# SCH_27C160-Replacement-Adapter_2025-10-2.net
KiCad netlist of a schematic drawn in EasyEDA
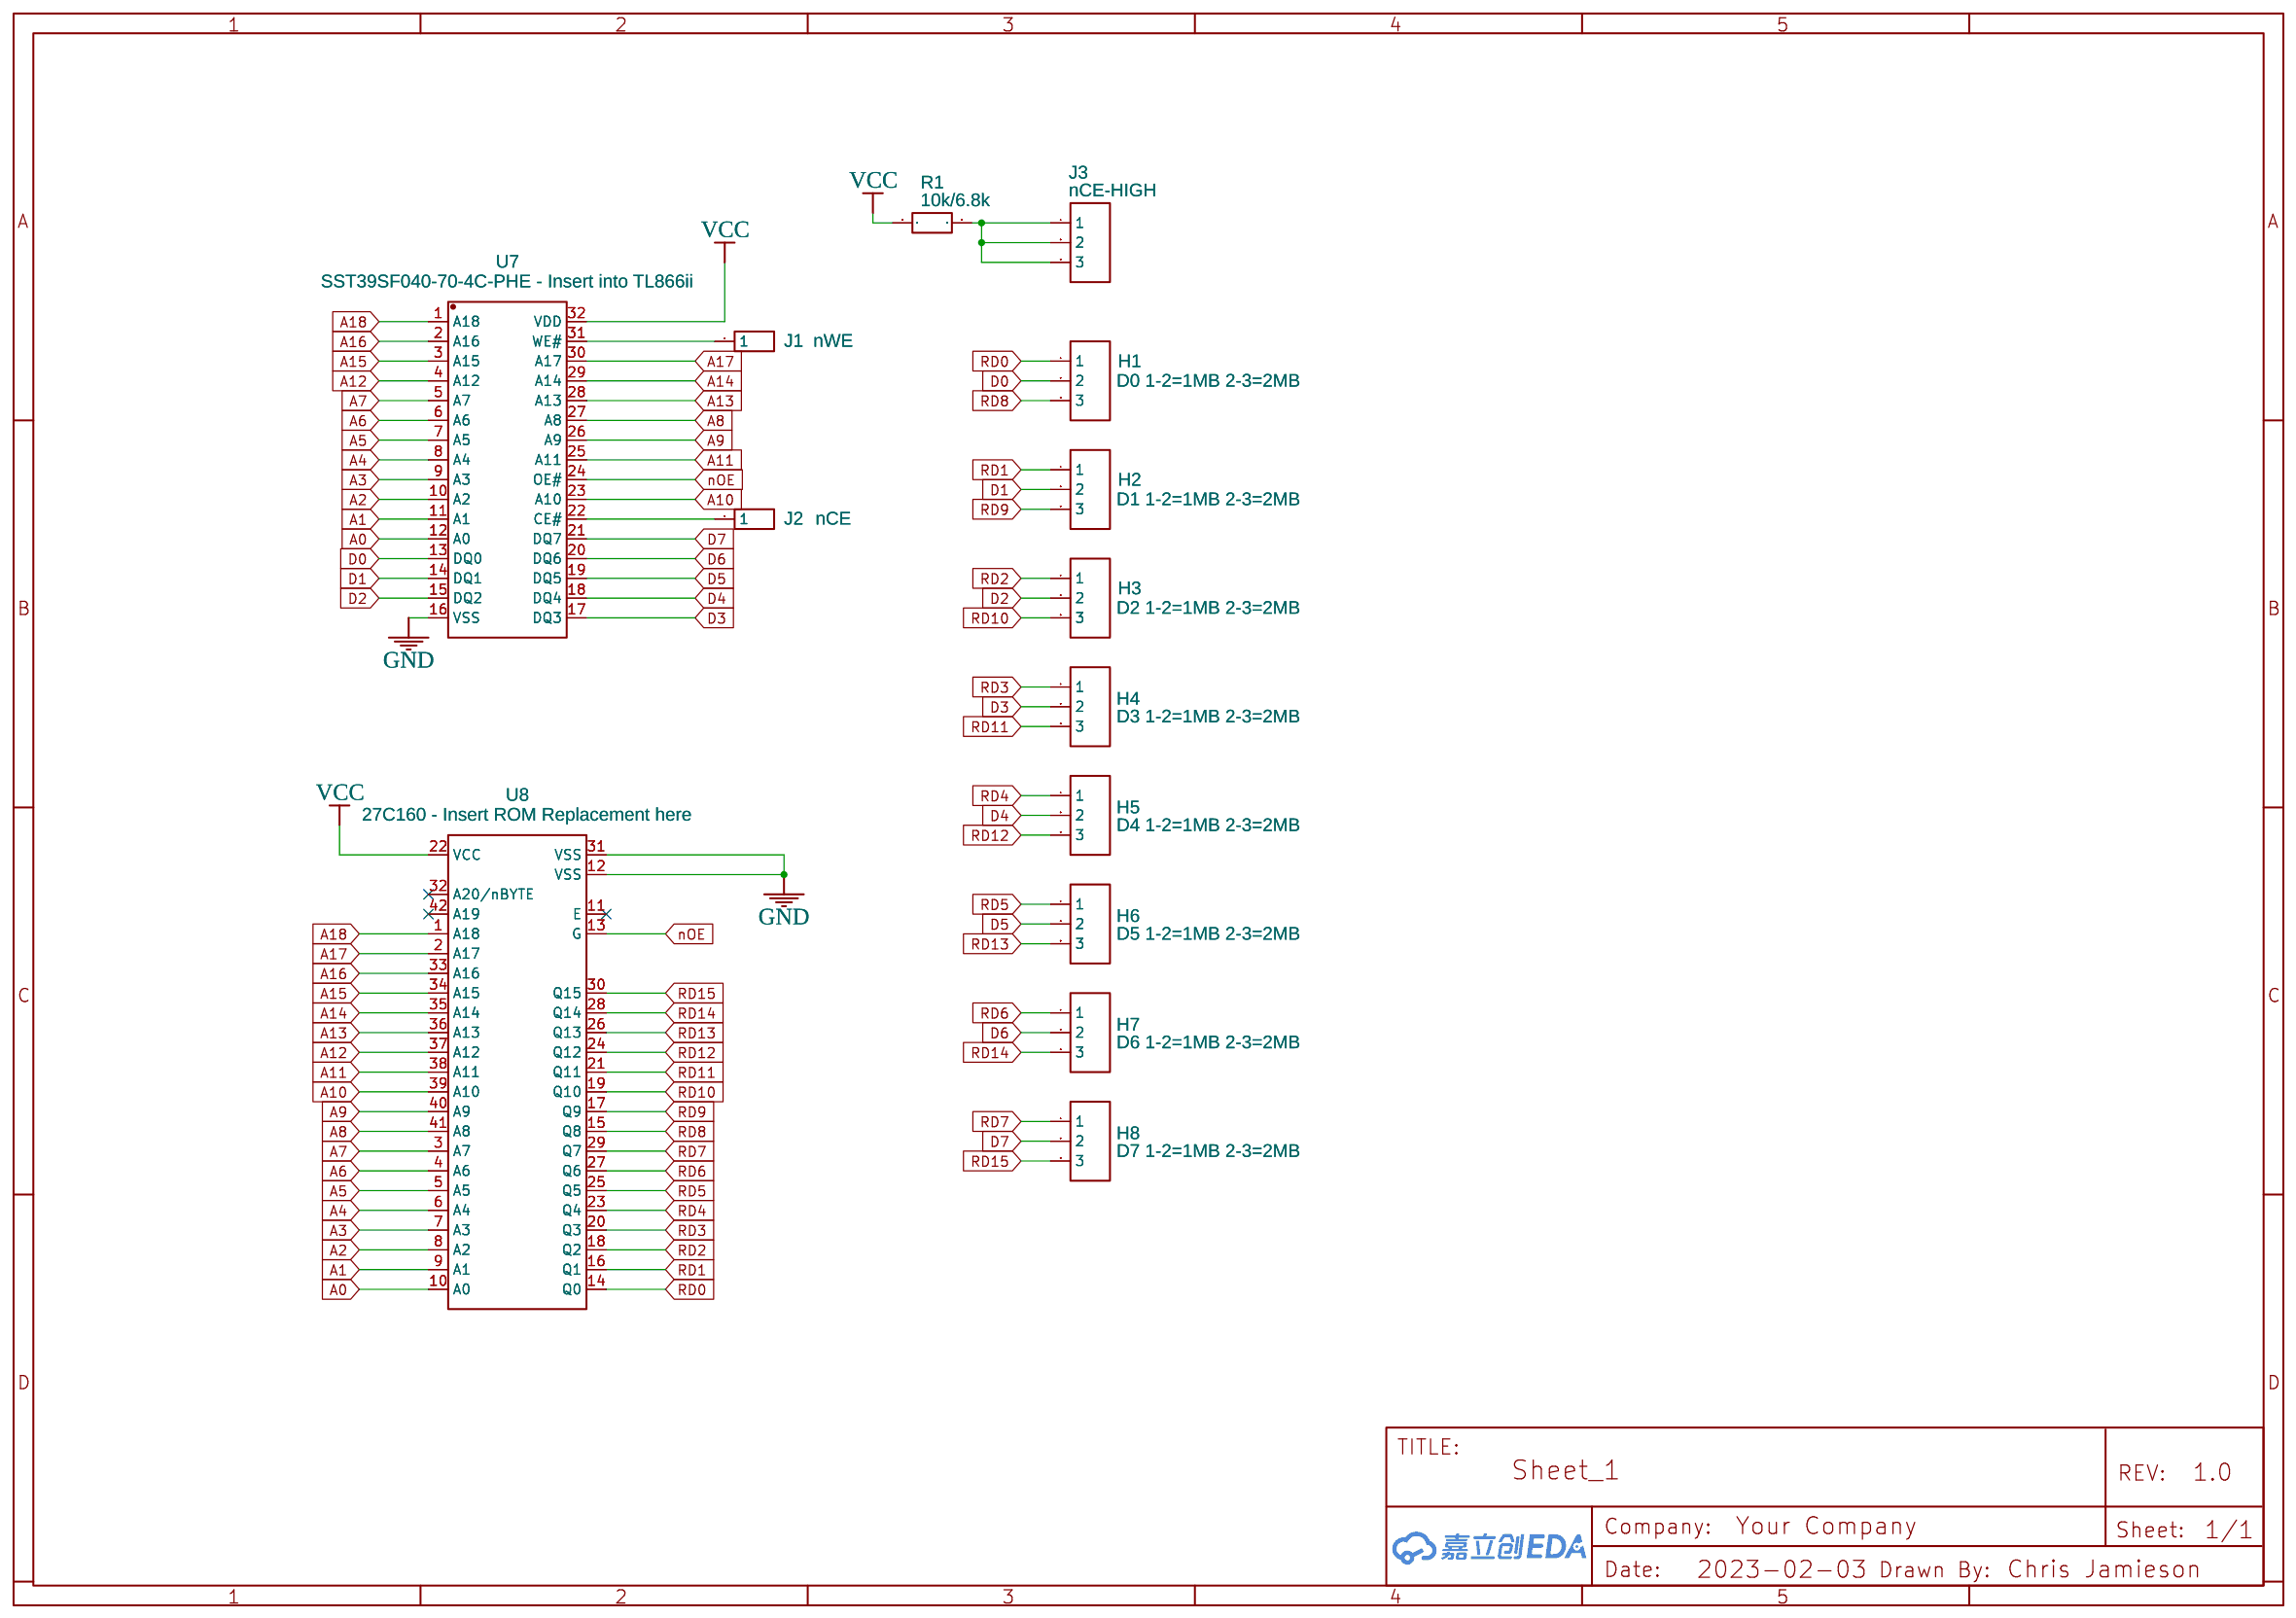
[diagram p0: schematic sheet]

(export (version "E")
  (design (tool "Eeschema 10.0.6"))
  (components
    (comp (ref "H1") (value "D0 1-2=1MB 2-3=2MB") (libsource (lib "") (part "HDR-F-2.54_1x3")))
    (comp (ref "H2") (value "D1 1-2=1MB 2-3=2MB") (libsource (lib "") (part "HDR-F-2.54_1x3")))
    (comp (ref "H3") (value "D2 1-2=1MB 2-3=2MB") (libsource (lib "") (part "HDR-F-2.54_1x3")))
    (comp (ref "H4") (value "D3 1-2=1MB 2-3=2MB") (libsource (lib "") (part "HDR-F-2.54_1x3")))
    (comp (ref "H5") (value "D4 1-2=1MB 2-3=2MB") (libsource (lib "") (part "HDR-F-2.54_1x3")))
    (comp (ref "H6") (value "D5 1-2=1MB 2-3=2MB") (libsource (lib "") (part "HDR-F-2.54_1x3")))
    (comp (ref "H7") (value "D6 1-2=1MB 2-3=2MB") (libsource (lib "") (part "HDR-F-2.54_1x3")))
    (comp (ref "H8") (value "D7 1-2=1MB 2-3=2MB") (libsource (lib "") (part "HDR-F-2.54_1x3")))
    (comp (ref "J1") (value "nWE") (libsource (lib "") (part "HDR-M-2.54_1x1")))
    (comp (ref "J2") (value "nCE") (libsource (lib "") (part "HDR-M-2.54_1x1")))
    (comp (ref "J3") (value "nCE-HIGH") (libsource (lib "") (part "HDR-M-2.54_1x3")))
    (comp (ref "R1") (value "10k/6.8k") (libsource (lib "") (part "R_AXIAL-0.4_EU")))
    (comp (ref "U7")
      (value "SST39SF040-70-4C-PHE - Insert into TL866ii")
      (fields
        (field (name "Manufacturer Part") "SST39SF040-70-4C-PHE")
        (field (name "Manufacturer") "MICROCHIP(美国微芯)")
      )
      (libsource (lib "") (part "SST39SF040-70-4C-PHE_C220176"))
    )
    (comp (ref "U8") (value "27C160 - Insert ROM Replacement here") (libsource (lib "") (part "M27C322")))
  )
  (nets
    (net (code "1") (name "A0") (class "Default")
      (node (ref "U7") (pin "12") (pinfunction "A0_12") (pintype "unspecified"))
      (node (ref "U8") (pin "10") (pinfunction "A0_10") (pintype "unspecified"))
    )
    (net (code "2") (name "A1") (class "Default")
      (node (ref "U7") (pin "11") (pinfunction "A1_11") (pintype "unspecified"))
      (node (ref "U8") (pin "9") (pinfunction "A1_9") (pintype "unspecified"))
    )
    (net (code "3") (name "A2") (class "Default")
      (node (ref "U7") (pin "10") (pinfunction "A2_10") (pintype "unspecified"))
      (node (ref "U8") (pin "8") (pinfunction "A2_8") (pintype "unspecified"))
    )
    (net (code "4") (name "A3") (class "Default")
      (node (ref "U7") (pin "9") (pinfunction "A3_9") (pintype "unspecified"))
      (node (ref "U8") (pin "7") (pinfunction "A3_7") (pintype "unspecified"))
    )
    (net (code "5") (name "A4") (class "Default")
      (node (ref "U7") (pin "8") (pinfunction "A4_8") (pintype "unspecified"))
      (node (ref "U8") (pin "6") (pinfunction "A4_6") (pintype "unspecified"))
    )
    (net (code "6") (name "A5") (class "Default")
      (node (ref "U7") (pin "7") (pinfunction "A5_7") (pintype "unspecified"))
      (node (ref "U8") (pin "5") (pinfunction "A5_5") (pintype "unspecified"))
    )
    (net (code "7") (name "A6") (class "Default")
      (node (ref "U7") (pin "6") (pinfunction "A6_6") (pintype "unspecified"))
      (node (ref "U8") (pin "4") (pinfunction "A6_4") (pintype "unspecified"))
    )
    (net (code "8") (name "A7") (class "Default")
      (node (ref "U7") (pin "5") (pinfunction "A7_5") (pintype "unspecified"))
      (node (ref "U8") (pin "3") (pinfunction "A7_3") (pintype "unspecified"))
    )
    (net (code "9") (name "A8") (class "Default")
      (node (ref "U7") (pin "27") (pinfunction "A8_27") (pintype "unspecified"))
      (node (ref "U8") (pin "41") (pinfunction "A8_41") (pintype "unspecified"))
    )
    (net (code "10") (name "A9") (class "Default")
      (node (ref "U7") (pin "26") (pinfunction "A9_26") (pintype "unspecified"))
      (node (ref "U8") (pin "40") (pinfunction "A9_40") (pintype "unspecified"))
    )
    (net (code "11") (name "A10") (class "Default")
      (node (ref "U7") (pin "23") (pinfunction "A10_23") (pintype "unspecified"))
      (node (ref "U8") (pin "39") (pinfunction "A10_39") (pintype "unspecified"))
    )
    (net (code "12") (name "A11") (class "Default")
      (node (ref "U7") (pin "25") (pinfunction "A11_25") (pintype "unspecified"))
      (node (ref "U8") (pin "38") (pinfunction "A11_38") (pintype "unspecified"))
    )
    (net (code "13") (name "A12") (class "Default")
      (node (ref "U7") (pin "4") (pinfunction "A12_4") (pintype "unspecified"))
      (node (ref "U8") (pin "37") (pinfunction "A12_37") (pintype "unspecified"))
    )
    (net (code "14") (name "A13") (class "Default")
      (node (ref "U7") (pin "28") (pinfunction "A13_28") (pintype "unspecified"))
      (node (ref "U8") (pin "36") (pinfunction "A13_36") (pintype "unspecified"))
    )
    (net (code "15") (name "A14") (class "Default")
      (node (ref "U7") (pin "29") (pinfunction "A14_29") (pintype "unspecified"))
      (node (ref "U8") (pin "35") (pinfunction "A14_35") (pintype "unspecified"))
    )
    (net (code "16") (name "A15") (class "Default")
      (node (ref "U7") (pin "3") (pinfunction "A15_3") (pintype "unspecified"))
      (node (ref "U8") (pin "34") (pinfunction "A15_34") (pintype "unspecified"))
    )
    (net (code "17") (name "A16") (class "Default")
      (node (ref "U7") (pin "2") (pinfunction "A16_2") (pintype "unspecified"))
      (node (ref "U8") (pin "33") (pinfunction "A16_33") (pintype "unspecified"))
    )
    (net (code "18") (name "A17") (class "Default")
      (node (ref "U7") (pin "30") (pinfunction "A17_30") (pintype "unspecified"))
      (node (ref "U8") (pin "2") (pinfunction "A17_2") (pintype "unspecified"))
    )
    (net (code "19") (name "A18") (class "Default")
      (node (ref "U7") (pin "1") (pinfunction "A18_1") (pintype "unspecified"))
      (node (ref "U8") (pin "1") (pinfunction "A18_1") (pintype "unspecified"))
    )
    (net (code "20") (name "D0") (class "Default")
      (node (ref "H1") (pin "2") (pinfunction "2_2") (pintype "input"))
      (node (ref "U7") (pin "13") (pinfunction "DQ0_13") (pintype "unspecified"))
    )
    (net (code "21") (name "D1") (class "Default")
      (node (ref "H2") (pin "2") (pinfunction "2_2") (pintype "input"))
      (node (ref "U7") (pin "14") (pinfunction "DQ1_14") (pintype "unspecified"))
    )
    (net (code "22") (name "D2") (class "Default")
      (node (ref "H3") (pin "2") (pinfunction "2_2") (pintype "input"))
      (node (ref "U7") (pin "15") (pinfunction "DQ2_15") (pintype "unspecified"))
    )
    (net (code "23") (name "D3") (class "Default")
      (node (ref "H4") (pin "2") (pinfunction "2_2") (pintype "input"))
      (node (ref "U7") (pin "17") (pinfunction "DQ3_17") (pintype "unspecified"))
    )
    (net (code "24") (name "D4") (class "Default")
      (node (ref "H5") (pin "2") (pinfunction "2_2") (pintype "input"))
      (node (ref "U7") (pin "18") (pinfunction "DQ4_18") (pintype "unspecified"))
    )
    (net (code "25") (name "D5") (class "Default")
      (node (ref "H6") (pin "2") (pinfunction "2_2") (pintype "input"))
      (node (ref "U7") (pin "19") (pinfunction "DQ5_19") (pintype "unspecified"))
    )
    (net (code "26") (name "D6") (class "Default")
      (node (ref "H7") (pin "2") (pinfunction "2_2") (pintype "input"))
      (node (ref "U7") (pin "20") (pinfunction "DQ6_20") (pintype "unspecified"))
    )
    (net (code "27") (name "D7") (class "Default")
      (node (ref "H8") (pin "2") (pinfunction "2_2") (pintype "input"))
      (node (ref "U7") (pin "21") (pinfunction "DQ7_21") (pintype "unspecified"))
    )
    (net (code "28") (name "GND") (class "Default")
      (node (ref "U7") (pin "16") (pinfunction "VSS_16") (pintype "unspecified"))
      (node (ref "U8") (pin "12") (pinfunction "VSS_12") (pintype "unspecified"))
      (node (ref "U8") (pin "31") (pinfunction "VSS_31") (pintype "unspecified"))
    )
    (net (code "29") (name "Net-(J3-Pad1)") (class "Default")
      (node (ref "J3") (pin "1") (pinfunction "1_1") (pintype "input"))
      (node (ref "J3") (pin "2") (pinfunction "2_2") (pintype "input"))
      (node (ref "J3") (pin "3") (pinfunction "3_3") (pintype "input"))
      (node (ref "R1") (pin "2") (pinfunction "2_2") (pintype "unspecified"))
    )
    (net (code "30") (name "Net-(U7-CE#)") (class "Default")
      (node (ref "J2") (pin "1") (pinfunction "1_1") (pintype "input"))
      (node (ref "U7") (pin "22") (pinfunction "CE#_22") (pintype "unspecified"))
    )
    (net (code "31") (name "Net-(U7-WE#)") (class "Default")
      (node (ref "J1") (pin "1") (pinfunction "1_1") (pintype "input"))
      (node (ref "U7") (pin "31") (pinfunction "WE#_31") (pintype "unspecified"))
    )
    (net (code "32") (name "RD0") (class "Default")
      (node (ref "H1") (pin "1") (pinfunction "1_1") (pintype "input"))
      (node (ref "U8") (pin "14") (pinfunction "Q0_14") (pintype "unspecified"))
    )
    (net (code "33") (name "RD1") (class "Default")
      (node (ref "H2") (pin "1") (pinfunction "1_1") (pintype "input"))
      (node (ref "U8") (pin "16") (pinfunction "Q1_16") (pintype "unspecified"))
    )
    (net (code "34") (name "RD2") (class "Default")
      (node (ref "H3") (pin "1") (pinfunction "1_1") (pintype "input"))
      (node (ref "U8") (pin "18") (pinfunction "Q2_18") (pintype "unspecified"))
    )
    (net (code "35") (name "RD3") (class "Default")
      (node (ref "H4") (pin "1") (pinfunction "1_1") (pintype "input"))
      (node (ref "U8") (pin "20") (pinfunction "Q3_20") (pintype "unspecified"))
    )
    (net (code "36") (name "RD4") (class "Default")
      (node (ref "H5") (pin "1") (pinfunction "1_1") (pintype "input"))
      (node (ref "U8") (pin "23") (pinfunction "Q4_23") (pintype "unspecified"))
    )
    (net (code "37") (name "RD5") (class "Default")
      (node (ref "H6") (pin "1") (pinfunction "1_1") (pintype "input"))
      (node (ref "U8") (pin "25") (pinfunction "Q5_25") (pintype "unspecified"))
    )
    (net (code "38") (name "RD6") (class "Default")
      (node (ref "H7") (pin "1") (pinfunction "1_1") (pintype "input"))
      (node (ref "U8") (pin "27") (pinfunction "Q6_27") (pintype "unspecified"))
    )
    (net (code "39") (name "RD7") (class "Default")
      (node (ref "H8") (pin "1") (pinfunction "1_1") (pintype "input"))
      (node (ref "U8") (pin "29") (pinfunction "Q7_29") (pintype "unspecified"))
    )
    (net (code "40") (name "RD8") (class "Default")
      (node (ref "H1") (pin "3") (pinfunction "3_3") (pintype "input"))
      (node (ref "U8") (pin "15") (pinfunction "Q8_15") (pintype "unspecified"))
    )
    (net (code "41") (name "RD9") (class "Default")
      (node (ref "H2") (pin "3") (pinfunction "3_3") (pintype "input"))
      (node (ref "U8") (pin "17") (pinfunction "Q9_17") (pintype "unspecified"))
    )
    (net (code "42") (name "RD10") (class "Default")
      (node (ref "H3") (pin "3") (pinfunction "3_3") (pintype "input"))
      (node (ref "U8") (pin "19") (pinfunction "Q10_19") (pintype "unspecified"))
    )
    (net (code "43") (name "RD11") (class "Default")
      (node (ref "H4") (pin "3") (pinfunction "3_3") (pintype "input"))
      (node (ref "U8") (pin "21") (pinfunction "Q11_21") (pintype "unspecified"))
    )
    (net (code "44") (name "RD12") (class "Default")
      (node (ref "H5") (pin "3") (pinfunction "3_3") (pintype "input"))
      (node (ref "U8") (pin "24") (pinfunction "Q12_24") (pintype "unspecified"))
    )
    (net (code "45") (name "RD13") (class "Default")
      (node (ref "H6") (pin "3") (pinfunction "3_3") (pintype "input"))
      (node (ref "U8") (pin "26") (pinfunction "Q13_26") (pintype "unspecified"))
    )
    (net (code "46") (name "RD14") (class "Default")
      (node (ref "H7") (pin "3") (pinfunction "3_3") (pintype "input"))
      (node (ref "U8") (pin "28") (pinfunction "Q14_28") (pintype "unspecified"))
    )
    (net (code "47") (name "RD15") (class "Default")
      (node (ref "H8") (pin "3") (pinfunction "3_3") (pintype "input"))
      (node (ref "U8") (pin "30") (pinfunction "Q15_30") (pintype "unspecified"))
    )
    (net (code "48") (name "VCC") (class "Default")
      (node (ref "R1") (pin "1") (pinfunction "1_1") (pintype "unspecified"))
      (node (ref "U7") (pin "32") (pinfunction "VDD_32") (pintype "unspecified"))
      (node (ref "U8") (pin "22") (pinfunction "VCC_22") (pintype "unspecified"))
    )
    (net (code "49") (name "nOE") (class "Default")
      (node (ref "U7") (pin "24") (pinfunction "OE#_24") (pintype "unspecified"))
      (node (ref "U8") (pin "13") (pinfunction "G_13") (pintype "unspecified"))
    )
    (net (code "50") (name "unconnected-(U8-A19-Pad42)") (class "Default")
      (node (ref "U8") (pin "42") (pinfunction "A19_42") (pintype "unspecified+no_connect"))
    )
    (net (code "51") (name "unconnected-(U8-A20{slash}nBYTE-Pad32)") (class "Default")
      (node (ref "U8") (pin "32") (pinfunction "A20/nBYTE_32") (pintype "unspecified+no_connect"))
    )
    (net (code "52") (name "unconnected-(U8-E-Pad11)") (class "Default")
      (node (ref "U8") (pin "11") (pinfunction "E_11") (pintype "unspecified+no_connect"))
    )
  )
)
